# STM32F030C8T6.net
KiCad netlist of a schematic drawn in Altium Designer
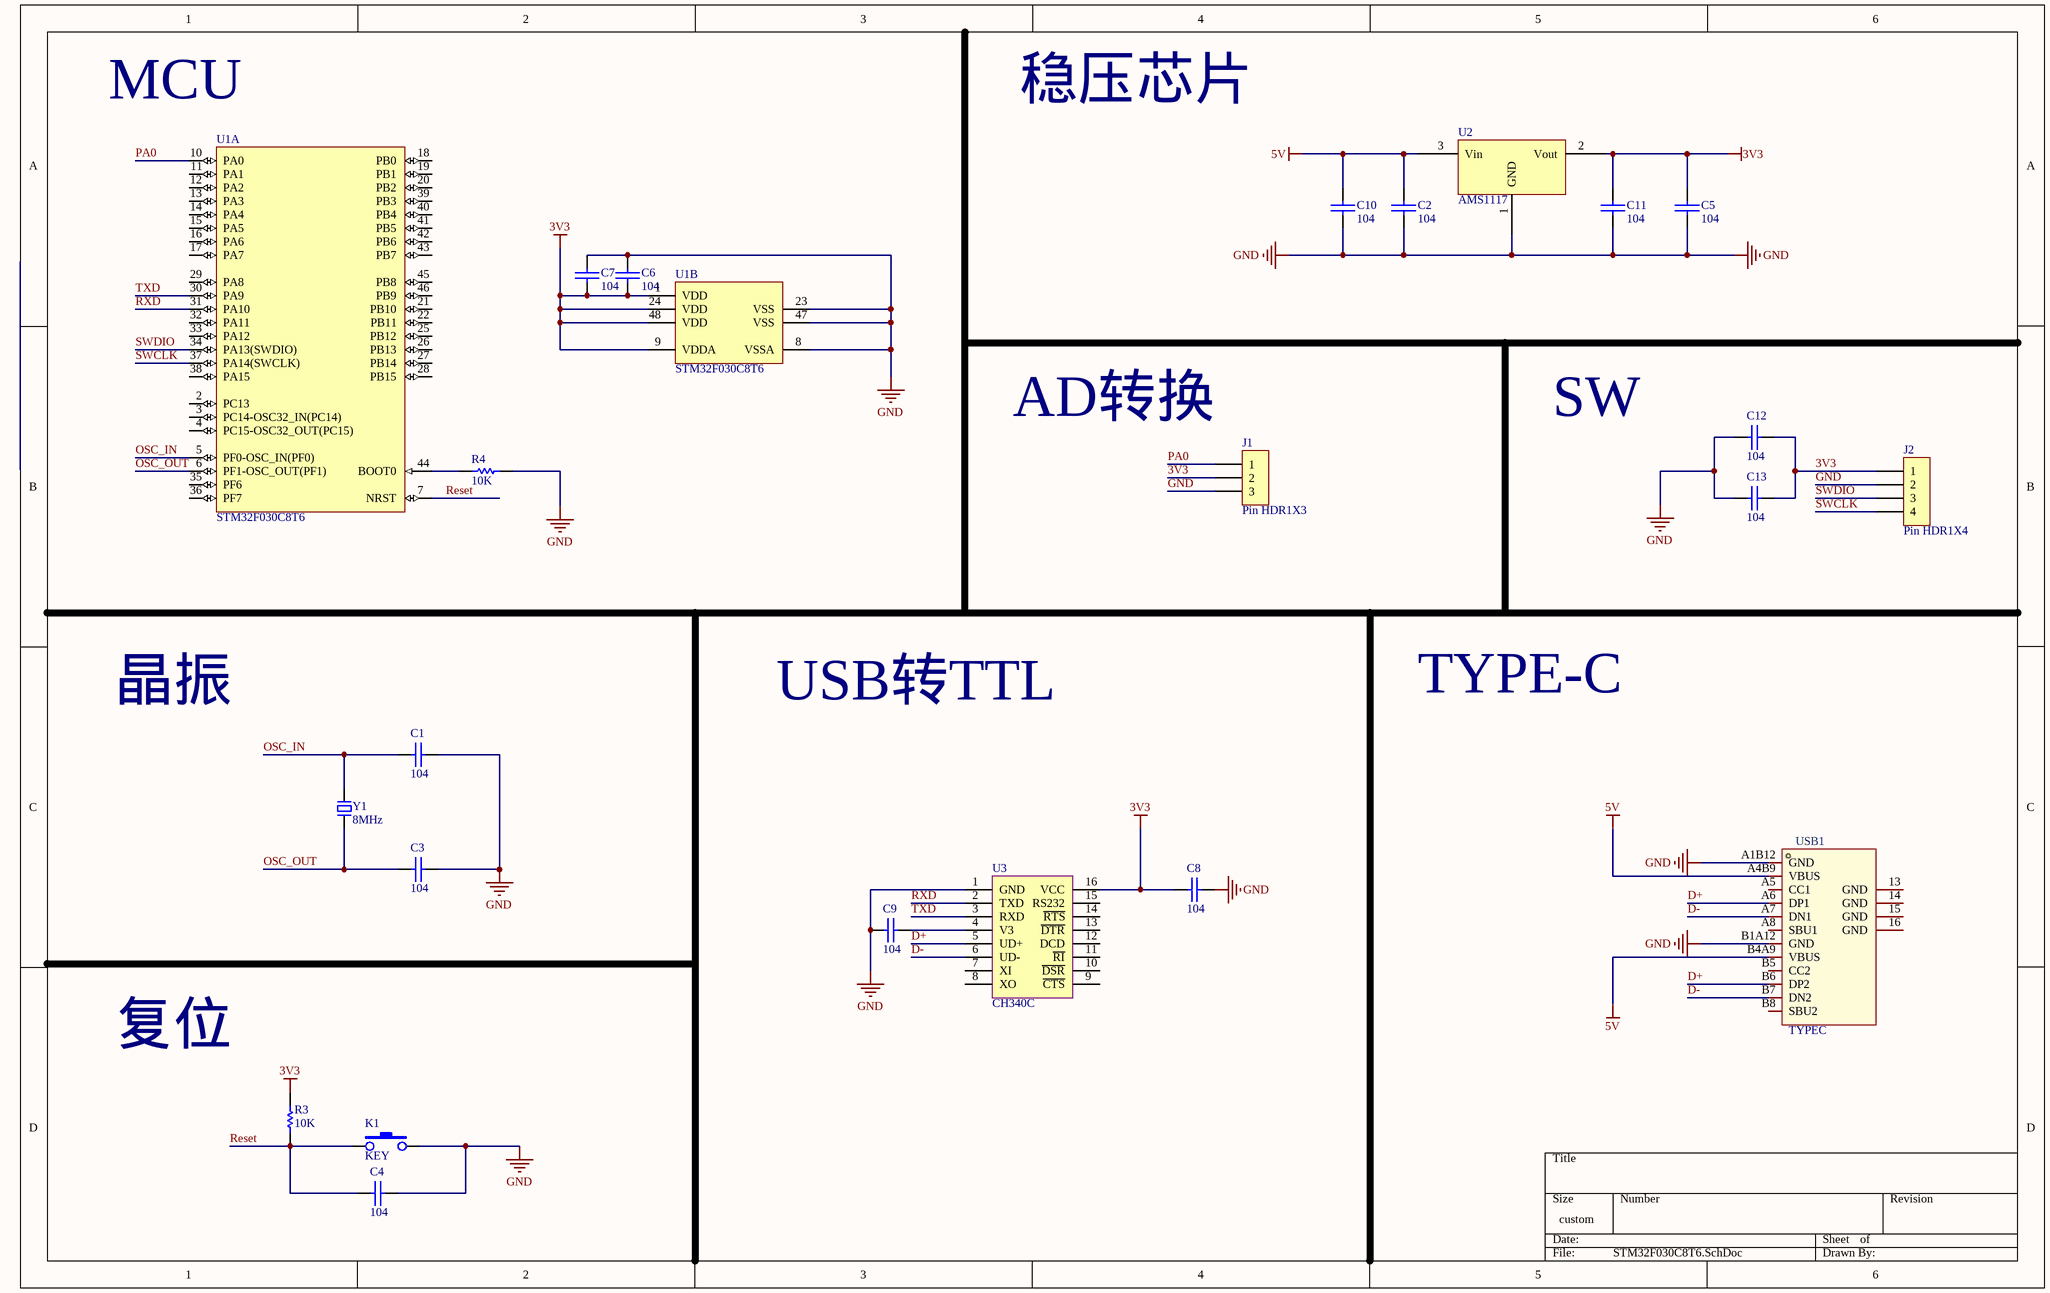
[diagram p0: STM32F030C8T6.SchDoc]

(export (version "E")
  (design (tool "Eeschema 10.0.6"))
  (components
    (comp (ref "C1")
      (value "104")
      (footprint "0805C")
      (description "无极性电容")
      (libsource (lib "电容") (part "CAP"))
    )
    (comp (ref "C2")
      (value "104")
      (footprint "0805C")
      (description "无极性电容")
      (libsource (lib "电容") (part "CAP"))
    )
    (comp (ref "C3")
      (value "104")
      (footprint "0805C")
      (description "无极性电容")
      (libsource (lib "电容") (part "CAP"))
    )
    (comp (ref "C4")
      (value "104")
      (footprint "0805C")
      (description "无极性电容")
      (libsource (lib "电容") (part "CAP"))
    )
    (comp (ref "C5")
      (value "104")
      (footprint "0805C")
      (description "无极性电容")
      (libsource (lib "电容") (part "CAP"))
    )
    (comp (ref "C6")
      (value "104")
      (footprint "0805C")
      (description "无极性电容")
      (libsource (lib "电容") (part "CAP"))
    )
    (comp (ref "C7")
      (value "104")
      (footprint "0805C")
      (description "无极性电容")
      (libsource (lib "电容") (part "CAP"))
    )
    (comp (ref "C8")
      (value "104")
      (footprint "0805C")
      (description "无极性电容")
      (libsource (lib "电容") (part "CAP"))
    )
    (comp (ref "C9")
      (value "104")
      (footprint "0805C")
      (description "无极性电容")
      (libsource (lib "电容") (part "CAP"))
    )
    (comp (ref "C10")
      (value "104")
      (footprint "0805C")
      (description "无极性电容")
      (libsource (lib "电容") (part "CAP"))
    )
    (comp (ref "C11")
      (value "104")
      (footprint "0805C")
      (description "无极性电容")
      (libsource (lib "电容") (part "CAP"))
    )
    (comp (ref "C12")
      (value "104")
      (footprint "0805C")
      (description "无极性电容")
      (libsource (lib "电容") (part "CAP"))
    )
    (comp (ref "C13")
      (value "104")
      (footprint "0805C")
      (description "无极性电容")
      (libsource (lib "电容") (part "CAP"))
    )
    (comp (ref "J1")
      (value "Pin HDR1X3")
      (footprint "Pin HDR1X3/2.54mm-S")
      (libsource (lib "排针") (part "Pin HDR1X3"))
    )
    (comp (ref "J2")
      (value "Pin HDR1X4")
      (footprint "Pin HDR1X4/2.54mm-S")
      (libsource (lib "排针") (part "Pin HDR1X4"))
    )
    (comp (ref "K1") (value "KEY") (footprint "SMD-3X6X2.5") (libsource (lib "轻触开关") (part "KEY")))
    (comp (ref "R3") (value "10K") (footprint "0805R") (libsource (lib "电阻") (part "RES")))
    (comp (ref "R4") (value "10K") (footprint "0805R") (libsource (lib "电阻") (part "RES")))
    (comp (ref "U1")
      (value "STM32F030C8T6")
      (footprint "STM-LQFP48_N")
      (libsource (lib "STMicroelectronics STM32 F0") (part "STM32F030C8T6"))
    )
    (comp (ref "U2")
      (value "AMS1117")
      (footprint "SOT223")
      (description "三端稳压芯片")
      (libsource (lib "电源芯片") (part "AMS1117"))
    )
    (comp (ref "U3")
      (value "CH340C")
      (footprint "SOP-16_L10.0-W3.9-P1.27-LS6.0-BL")
      (libsource (lib "通讯系列IC") (part "CH340G"))
    )
    (comp (ref "USB1")
      (value "TYPEC")
      (footprint "USB-C-SMD_TYPEC-304-BCP16")
      (fields (field (name "MANUFACTURER") "XUNPU(讯普)") (field (name "MANUFACTURER PART") "TYPEC-304-BCP16"))
      (libsource (lib "TYPEC") (part "TYPEC-304-BCP16_C720629"))
    )
    (comp (ref "Y1")
      (value "8MHz")
      (footprint "OSC 5032-2P")
      (description "2脚无源脚晶振")
      (libsource (lib "晶振") (part "XTAL-2P"))
    )
  )
  (nets
    (net (code "1") (name "/D+") (class "Default")
      (node (ref "U3") (pin "5") (pinfunction "UD+_5") (pintype "passive"))
      (node (ref "USB1") (pin "A6") (pinfunction "DP1_A6") (pintype "passive"))
      (node (ref "USB1") (pin "B6") (pinfunction "DP2_B6") (pintype "passive"))
    )
    (net (code "2") (name "/D-") (class "Default")
      (node (ref "U3") (pin "6") (pinfunction "UD-_6") (pintype "passive"))
      (node (ref "USB1") (pin "A7") (pinfunction "DN1_A7") (pintype "passive"))
      (node (ref "USB1") (pin "B7") (pinfunction "DN2_B7") (pintype "passive"))
    )
    (net (code "3") (name "/OSC_IN") (class "Default")
      (node (ref "C1") (pin "1") (pinfunction "1_1") (pintype "passive"))
      (node (ref "U1") (pin "5") (pinfunction "PF0-OSC_IN(PF0)_5") (pintype "bidirectional"))
      (node (ref "Y1") (pin "2") (pinfunction "2_2") (pintype "passive"))
    )
    (net (code "4") (name "/OSC_OUT") (class "Default")
      (node (ref "C3") (pin "1") (pinfunction "1_1") (pintype "passive"))
      (node (ref "U1") (pin "6") (pinfunction "PF1-OSC_OUT(PF1)_6") (pintype "bidirectional"))
      (node (ref "Y1") (pin "1") (pinfunction "1_1") (pintype "passive"))
    )
    (net (code "5") (name "/PA0") (class "Default")
      (node (ref "J1") (pin "1") (pinfunction "1_1") (pintype "passive"))
      (node (ref "U1") (pin "10") (pinfunction "PA0_10") (pintype "bidirectional"))
    )
    (net (code "6") (name "/RXD") (class "Default")
      (node (ref "U1") (pin "31") (pinfunction "PA10_31") (pintype "bidirectional"))
      (node (ref "U3") (pin "2") (pinfunction "TXD_2") (pintype "passive"))
    )
    (net (code "7") (name "/Reset") (class "Default")
      (node (ref "C4") (pin "1") (pinfunction "1_1") (pintype "passive"))
      (node (ref "K1") (pin "1") (pinfunction "1_1") (pintype "passive"))
      (node (ref "R3") (pin "1") (pinfunction "1_1") (pintype "passive"))
      (node (ref "U1") (pin "7") (pinfunction "NRST_7") (pintype "bidirectional"))
    )
    (net (code "8") (name "/SWCLK") (class "Default")
      (node (ref "J2") (pin "4") (pinfunction "4_4") (pintype "passive"))
      (node (ref "U1") (pin "37") (pinfunction "PA14(SWCLK)_37") (pintype "bidirectional"))
    )
    (net (code "9") (name "/SWDIO") (class "Default")
      (node (ref "J2") (pin "3") (pinfunction "3_3") (pintype "passive"))
      (node (ref "U1") (pin "34") (pinfunction "PA13(SWDIO)_34") (pintype "bidirectional"))
    )
    (net (code "10") (name "/TXD") (class "Default")
      (node (ref "U1") (pin "30") (pinfunction "PA9_30") (pintype "bidirectional"))
      (node (ref "U3") (pin "3") (pinfunction "RXD_3") (pintype "passive"))
    )
    (net (code "11") (name "3V3") (class "Default")
      (node (ref "C11") (pin "1") (pinfunction "1_1") (pintype "passive"))
      (node (ref "C12") (pin "2") (pinfunction "2_2") (pintype "passive"))
      (node (ref "C13") (pin "2") (pinfunction "2_2") (pintype "passive"))
      (node (ref "C5") (pin "1") (pinfunction "1_1") (pintype "passive"))
      (node (ref "C6") (pin "2") (pinfunction "2_2") (pintype "passive"))
      (node (ref "C7") (pin "2") (pinfunction "2_2") (pintype "passive"))
      (node (ref "C8") (pin "1") (pinfunction "1_1") (pintype "passive"))
      (node (ref "J1") (pin "2") (pinfunction "2_2") (pintype "passive"))
      (node (ref "J2") (pin "1") (pinfunction "1_1") (pintype "passive"))
      (node (ref "R3") (pin "2") (pinfunction "2_2") (pintype "passive"))
      (node (ref "U1") (pin "1") (pinfunction "VDD_1") (pintype "power_in"))
      (node (ref "U1") (pin "24") (pinfunction "VDD_24") (pintype "power_in"))
      (node (ref "U1") (pin "48") (pinfunction "VDD_48") (pintype "power_in"))
      (node (ref "U1") (pin "9") (pinfunction "VDDA_9") (pintype "power_in"))
      (node (ref "U2") (pin "2") (pinfunction "Vout_2") (pintype "passive"))
      (node (ref "U3") (pin "16") (pinfunction "VCC_16") (pintype "passive"))
    )
    (net (code "12") (name "5V") (class "Default")
      (node (ref "C10") (pin "1") (pinfunction "1_1") (pintype "passive"))
      (node (ref "C2") (pin "1") (pinfunction "1_1") (pintype "passive"))
      (node (ref "U2") (pin "3") (pinfunction "Vin_3") (pintype "passive"))
      (node (ref "USB1") (pin "A4B9") (pinfunction "VBUS_A4B9") (pintype "passive"))
      (node (ref "USB1") (pin "B4A9") (pinfunction "VBUS_B4A9") (pintype "passive"))
    )
    (net (code "13") (name "GND") (class "Default")
      (node (ref "C1") (pin "2") (pinfunction "2_2") (pintype "passive"))
      (node (ref "C10") (pin "2") (pinfunction "2_2") (pintype "passive"))
      (node (ref "C11") (pin "2") (pinfunction "2_2") (pintype "passive"))
      (node (ref "C12") (pin "1") (pinfunction "1_1") (pintype "passive"))
      (node (ref "C13") (pin "1") (pinfunction "1_1") (pintype "passive"))
      (node (ref "C2") (pin "2") (pinfunction "2_2") (pintype "passive"))
      (node (ref "C3") (pin "2") (pinfunction "2_2") (pintype "passive"))
      (node (ref "C4") (pin "2") (pinfunction "2_2") (pintype "passive"))
      (node (ref "C5") (pin "2") (pinfunction "2_2") (pintype "passive"))
      (node (ref "C6") (pin "1") (pinfunction "1_1") (pintype "passive"))
      (node (ref "C7") (pin "1") (pinfunction "1_1") (pintype "passive"))
      (node (ref "C8") (pin "2") (pinfunction "2_2") (pintype "passive"))
      (node (ref "C9") (pin "1") (pinfunction "1_1") (pintype "passive"))
      (node (ref "J1") (pin "3") (pinfunction "3_3") (pintype "passive"))
      (node (ref "J2") (pin "2") (pinfunction "2_2") (pintype "passive"))
      (node (ref "K1") (pin "3") (pinfunction "3_3") (pintype "passive"))
      (node (ref "R4") (pin "2") (pinfunction "2_2") (pintype "passive"))
      (node (ref "U1") (pin "23") (pinfunction "VSS_23") (pintype "power_in"))
      (node (ref "U1") (pin "47") (pinfunction "VSS_47") (pintype "power_in"))
      (node (ref "U1") (pin "8") (pinfunction "VSSA_8") (pintype "power_in"))
      (node (ref "U2") (pin "1") (pinfunction "GND_1") (pintype "passive"))
      (node (ref "U3") (pin "1") (pinfunction "GND_1") (pintype "passive"))
      (node (ref "USB1") (pin "A1B12") (pinfunction "GND_A1B12") (pintype "passive"))
      (node (ref "USB1") (pin "B1A12") (pinfunction "GND_B1A12") (pintype "passive"))
    )
    (net (code "14") (name "Net-(U1A-BOOT0)") (class "Default")
      (node (ref "R4") (pin "1") (pinfunction "1_1") (pintype "passive"))
      (node (ref "U1") (pin "44") (pinfunction "BOOT0_44") (pintype "input"))
    )
    (net (code "15") (name "Net-(U3-V3)") (class "Default")
      (node (ref "C9") (pin "2") (pinfunction "2_2") (pintype "passive"))
      (node (ref "U3") (pin "4") (pinfunction "V3_4") (pintype "passive"))
    )
    (net (code "16") (name "unconnected-(U1A-PA1-Pad11)") (class "Default")
      (node (ref "U1") (pin "11") (pinfunction "PA1_11") (pintype "bidirectional"))
    )
    (net (code "17") (name "unconnected-(U1A-PA2-Pad12)") (class "Default")
      (node (ref "U1") (pin "12") (pinfunction "PA2_12") (pintype "bidirectional"))
    )
    (net (code "18") (name "unconnected-(U1A-PA3-Pad13)") (class "Default")
      (node (ref "U1") (pin "13") (pinfunction "PA3_13") (pintype "bidirectional"))
    )
    (net (code "19") (name "unconnected-(U1A-PA4-Pad14)") (class "Default")
      (node (ref "U1") (pin "14") (pinfunction "PA4_14") (pintype "bidirectional"))
    )
    (net (code "20") (name "unconnected-(U1A-PA5-Pad15)") (class "Default")
      (node (ref "U1") (pin "15") (pinfunction "PA5_15") (pintype "bidirectional"))
    )
    (net (code "21") (name "unconnected-(U1A-PA6-Pad16)") (class "Default")
      (node (ref "U1") (pin "16") (pinfunction "PA6_16") (pintype "bidirectional"))
    )
    (net (code "22") (name "unconnected-(U1A-PA7-Pad17)") (class "Default")
      (node (ref "U1") (pin "17") (pinfunction "PA7_17") (pintype "bidirectional"))
    )
    (net (code "23") (name "unconnected-(U1A-PA8-Pad29)") (class "Default")
      (node (ref "U1") (pin "29") (pinfunction "PA8_29") (pintype "bidirectional"))
    )
    (net (code "24") (name "unconnected-(U1A-PA11-Pad32)") (class "Default")
      (node (ref "U1") (pin "32") (pinfunction "PA11_32") (pintype "bidirectional"))
    )
    (net (code "25") (name "unconnected-(U1A-PA12-Pad33)") (class "Default")
      (node (ref "U1") (pin "33") (pinfunction "PA12_33") (pintype "bidirectional"))
    )
    (net (code "26") (name "unconnected-(U1A-PA15-Pad38)") (class "Default")
      (node (ref "U1") (pin "38") (pinfunction "PA15_38") (pintype "bidirectional"))
    )
    (net (code "27") (name "unconnected-(U1A-PB0-Pad18)") (class "Default")
      (node (ref "U1") (pin "18") (pinfunction "PB0_18") (pintype "bidirectional"))
    )
    (net (code "28") (name "unconnected-(U1A-PB1-Pad19)") (class "Default")
      (node (ref "U1") (pin "19") (pinfunction "PB1_19") (pintype "bidirectional"))
    )
    (net (code "29") (name "unconnected-(U1A-PB2-Pad20)") (class "Default")
      (node (ref "U1") (pin "20") (pinfunction "PB2_20") (pintype "bidirectional"))
    )
    (net (code "30") (name "unconnected-(U1A-PB3-Pad39)") (class "Default")
      (node (ref "U1") (pin "39") (pinfunction "PB3_39") (pintype "bidirectional"))
    )
    (net (code "31") (name "unconnected-(U1A-PB4-Pad40)") (class "Default")
      (node (ref "U1") (pin "40") (pinfunction "PB4_40") (pintype "bidirectional"))
    )
    (net (code "32") (name "unconnected-(U1A-PB5-Pad41)") (class "Default")
      (node (ref "U1") (pin "41") (pinfunction "PB5_41") (pintype "bidirectional"))
    )
    (net (code "33") (name "unconnected-(U1A-PB6-Pad42)") (class "Default")
      (node (ref "U1") (pin "42") (pinfunction "PB6_42") (pintype "bidirectional"))
    )
    (net (code "34") (name "unconnected-(U1A-PB7-Pad43)") (class "Default")
      (node (ref "U1") (pin "43") (pinfunction "PB7_43") (pintype "bidirectional"))
    )
    (net (code "35") (name "unconnected-(U1A-PB8-Pad45)") (class "Default")
      (node (ref "U1") (pin "45") (pinfunction "PB8_45") (pintype "bidirectional"))
    )
    (net (code "36") (name "unconnected-(U1A-PB9-Pad46)") (class "Default")
      (node (ref "U1") (pin "46") (pinfunction "PB9_46") (pintype "bidirectional"))
    )
    (net (code "37") (name "unconnected-(U1A-PB10-Pad21)") (class "Default")
      (node (ref "U1") (pin "21") (pinfunction "PB10_21") (pintype "bidirectional"))
    )
    (net (code "38") (name "unconnected-(U1A-PB11-Pad22)") (class "Default")
      (node (ref "U1") (pin "22") (pinfunction "PB11_22") (pintype "bidirectional"))
    )
    (net (code "39") (name "unconnected-(U1A-PB12-Pad25)") (class "Default")
      (node (ref "U1") (pin "25") (pinfunction "PB12_25") (pintype "bidirectional"))
    )
    (net (code "40") (name "unconnected-(U1A-PB13-Pad26)") (class "Default")
      (node (ref "U1") (pin "26") (pinfunction "PB13_26") (pintype "bidirectional"))
    )
    (net (code "41") (name "unconnected-(U1A-PB14-Pad27)") (class "Default")
      (node (ref "U1") (pin "27") (pinfunction "PB14_27") (pintype "bidirectional"))
    )
    (net (code "42") (name "unconnected-(U1A-PB15-Pad28)") (class "Default")
      (node (ref "U1") (pin "28") (pinfunction "PB15_28") (pintype "bidirectional"))
    )
    (net (code "43") (name "unconnected-(U1A-PC13-Pad2)") (class "Default")
      (node (ref "U1") (pin "2") (pinfunction "PC13_2") (pintype "bidirectional"))
    )
    (net (code "44") (name "unconnected-(U1A-PC14-OSC32_IN(PC14)-Pad3)") (class "Default")
      (node (ref "U1") (pin "3") (pinfunction "PC14-OSC32_IN(PC14)_3") (pintype "bidirectional"))
    )
    (net (code "45") (name "unconnected-(U1A-PC15-OSC32_OUT(PC15)-Pad4)") (class "Default")
      (node (ref "U1") (pin "4") (pinfunction "PC15-OSC32_OUT(PC15)_4") (pintype "bidirectional"))
    )
    (net (code "46") (name "unconnected-(U1A-PF6-Pad35)") (class "Default")
      (node (ref "U1") (pin "35") (pinfunction "PF6_35") (pintype "bidirectional"))
    )
    (net (code "47") (name "unconnected-(U1A-PF7-Pad36)") (class "Default")
      (node (ref "U1") (pin "36") (pinfunction "PF7_36") (pintype "bidirectional"))
    )
    (net (code "48") (name "unconnected-(U3-DCD-Pad12)") (class "Default")
      (node (ref "U3") (pin "12") (pinfunction "DCD_12") (pintype "passive"))
    )
    (net (code "49") (name "unconnected-(U3-RS232-Pad15)") (class "Default")
      (node (ref "U3") (pin "15") (pinfunction "RS232_15") (pintype "passive"))
    )
    (net (code "50") (name "unconnected-(U3-XI-Pad7)") (class "Default")
      (node (ref "U3") (pin "7") (pinfunction "XI_7") (pintype "passive"))
    )
    (net (code "51") (name "unconnected-(U3-XO-Pad8)") (class "Default")
      (node (ref "U3") (pin "8") (pinfunction "XO_8") (pintype "passive"))
    )
    (net (code "52") (name "unconnected-(U3-~{CTS}-Pad9)") (class "Default")
      (node (ref "U3") (pin "9") (pinfunction "~{CTS}_9") (pintype "passive"))
    )
    (net (code "53") (name "unconnected-(U3-~{DSR}-Pad10)") (class "Default")
      (node (ref "U3") (pin "10") (pinfunction "~{DSR}_10") (pintype "passive"))
    )
    (net (code "54") (name "unconnected-(U3-~{DTR}-Pad13)") (class "Default")
      (node (ref "U3") (pin "13") (pinfunction "~{DTR}_13") (pintype "passive"))
    )
    (net (code "55") (name "unconnected-(U3-~{RI}-Pad11)") (class "Default")
      (node (ref "U3") (pin "11") (pinfunction "~{RI}_11") (pintype "passive"))
    )
    (net (code "56") (name "unconnected-(U3-~{RTS}-Pad14)") (class "Default")
      (node (ref "U3") (pin "14") (pinfunction "~{RTS}_14") (pintype "passive"))
    )
    (net (code "57") (name "unconnected-(USB1-CC1-PadA5)") (class "Default")
      (node (ref "USB1") (pin "A5") (pinfunction "CC1_A5") (pintype "passive"))
    )
    (net (code "58") (name "unconnected-(USB1-CC2-PadB5)") (class "Default")
      (node (ref "USB1") (pin "B5") (pinfunction "CC2_B5") (pintype "passive"))
    )
    (net (code "59") (name "unconnected-(USB1-GND-Pad13)") (class "Default")
      (node (ref "USB1") (pin "13") (pinfunction "GND_13") (pintype "passive"))
    )
    (net (code "60") (name "unconnected-(USB1-GND-Pad14)") (class "Default")
      (node (ref "USB1") (pin "14") (pinfunction "GND_14") (pintype "passive"))
    )
    (net (code "61") (name "unconnected-(USB1-GND-Pad15)") (class "Default")
      (node (ref "USB1") (pin "15") (pinfunction "GND_15") (pintype "passive"))
    )
    (net (code "62") (name "unconnected-(USB1-GND-Pad16)") (class "Default")
      (node (ref "USB1") (pin "16") (pinfunction "GND_16") (pintype "passive"))
    )
    (net (code "63") (name "unconnected-(USB1-SBU1-PadA8)") (class "Default")
      (node (ref "USB1") (pin "A8") (pinfunction "SBU1_A8") (pintype "passive"))
    )
    (net (code "64") (name "unconnected-(USB1-SBU2-PadB8)") (class "Default")
      (node (ref "USB1") (pin "B8") (pinfunction "SBU2_B8") (pintype "passive"))
    )
  )
)
